# regulators.net
KiCad netlist of a schematic drawn in Altium Designer
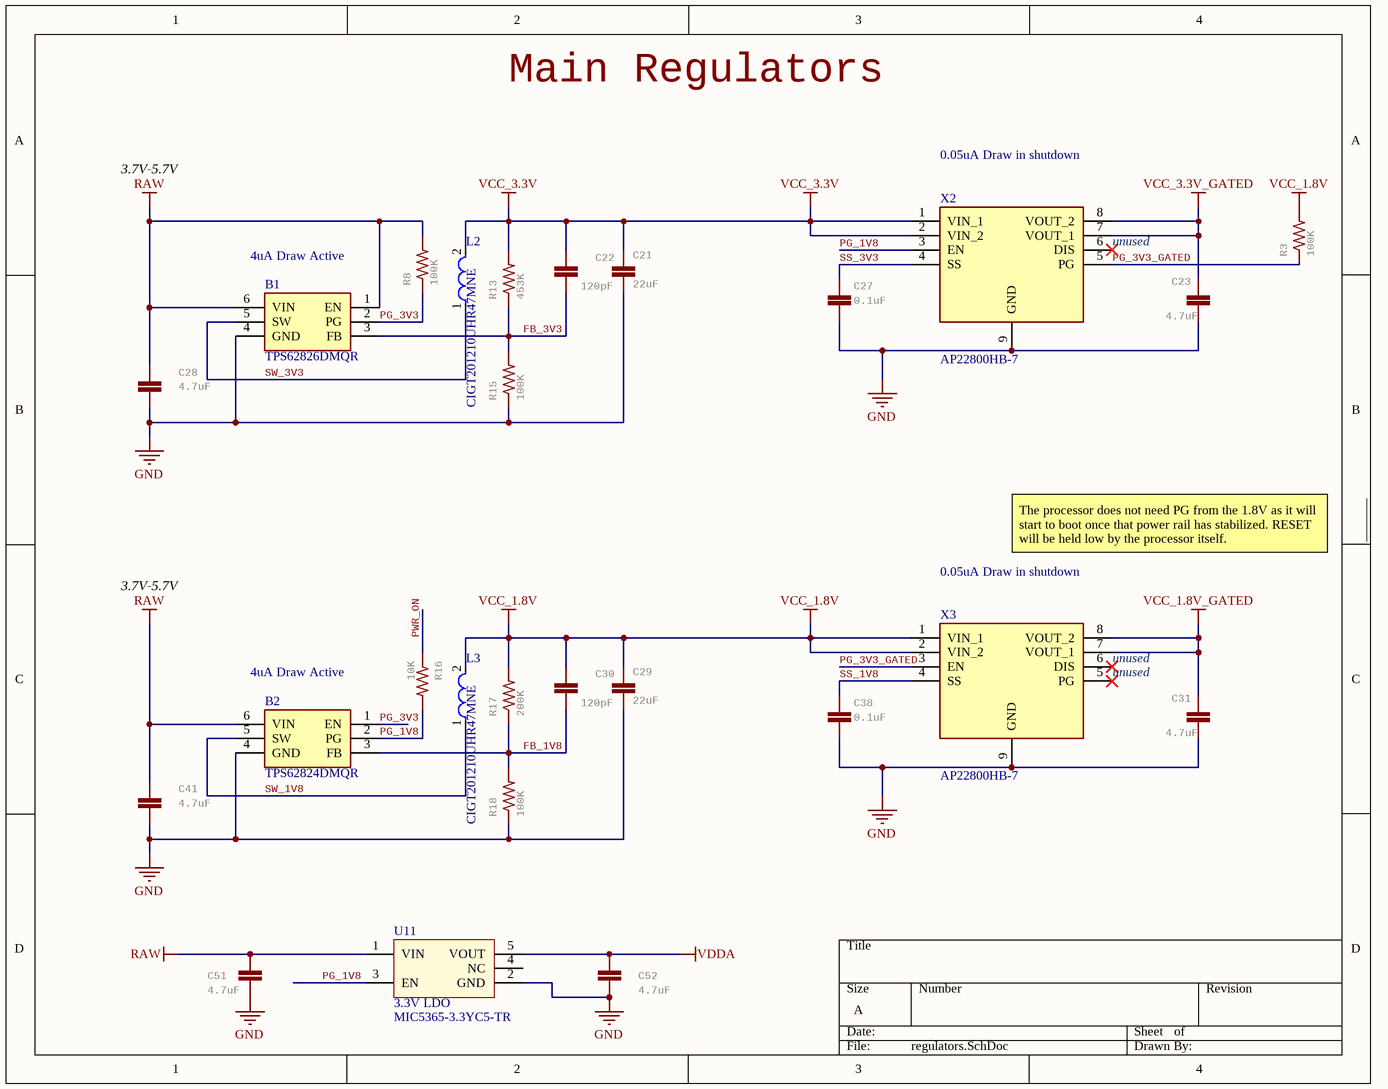
[diagram p0: regulators.SchDoc]

(export (version "E")
  (design (tool "Eeschema 10.0.6"))
  (components
    (comp (ref "B1")
      (value "TPS62826DMQR")
      (footprint "TPS62826ADMQR")
      (fields (field (name "MOUSER PART NUMBER") "595-TPS62826DMQR"))
      (libsource (lib "openmv-ae3") (part "TPS62826ADMQR"))
    )
    (comp (ref "B2")
      (value "TPS62824DMQR")
      (footprint "TPS62826ADMQR")
      (fields (field (name "MOUSER PART NUMBER") "595-TPS62824DMQR"))
      (libsource (lib "openmv-ae3") (part "TPS62826ADMQR"))
    )
    (comp (ref "C21")
      (value "22uF")
      (footprint "0805")
      (fields (field (name "MPN") "CL21A226MQQNNNE"))
      (libsource (lib "openmv-ae3") (part "22UF-0805-6.3V-20%"))
    )
    (comp (ref "C22")
      (value "120pF")
      (footprint "0402-CAP")
      (description "CapacitorStandard 0603 ceramic capacitor, and 0.1\" leaded capacitor.")
      (fields (field (name "MPN") "GRM1555C2A121GE01D"))
      (libsource (lib "openmv-ae3") (part "CAP0402-CAP"))
    )
    (comp (ref "C23")
      (value "4.7uF")
      (footprint "0402-CAP")
      (description "CapacitorStandard 0603 ceramic capacitor, and 0.1\" leaded capacitor.")
      (fields (field (name "MPN") "JMK105BBJ475MV-F"))
      (libsource (lib "") (part "CAP0402-CAP_1"))
    )
    (comp (ref "C27")
      (value "0.1uF")
      (footprint "0402-CAP")
      (description "CAPACITOR, European symbol")
      (fields (field (name "MPN") "C0402C104Z4VAC"))
      (libsource (lib "rt10") (part "C-EUC0201"))
    )
    (comp (ref "C28")
      (value "4.7uF")
      (footprint "0402-CAP")
      (description "CapacitorStandard 0603 ceramic capacitor, and 0.1\" leaded capacitor.")
      (fields (field (name "MPN") "JMK105BBJ475MV-F"))
      (libsource (lib "openmv-ae3") (part "CAP0402-CAP"))
    )
    (comp (ref "C29")
      (value "22uF")
      (footprint "0805")
      (fields (field (name "MPN") "CL21A226MQQNNNE"))
      (libsource (lib "openmv-ae3") (part "22UF-0805-6.3V-20%"))
    )
    (comp (ref "C30")
      (value "120pF")
      (footprint "0402-CAP")
      (description "CapacitorStandard 0603 ceramic capacitor, and 0.1\" leaded capacitor.")
      (fields (field (name "MPN") "GRM1555C2A121GE01D"))
      (libsource (lib "openmv-ae3") (part "CAP0402-CAP"))
    )
    (comp (ref "C31")
      (value "4.7uF")
      (footprint "0402-CAP")
      (description "CapacitorStandard 0603 ceramic capacitor, and 0.1\" leaded capacitor.")
      (fields (field (name "MPN") "JMK105BBJ475MV-F"))
      (libsource (lib "") (part "CAP0402-CAP_1"))
    )
    (comp (ref "C38")
      (value "0.1uF")
      (footprint "0402-CAP")
      (description "CAPACITOR, European symbol")
      (fields (field (name "MPN") "C0402C104Z4VAC"))
      (libsource (lib "rt10") (part "C-EUC0201"))
    )
    (comp (ref "C41")
      (value "4.7uF")
      (footprint "0402-CAP")
      (description "CapacitorStandard 0603 ceramic capacitor, and 0.1\" leaded capacitor.")
      (fields (field (name "MPN") "JMK105BBJ475MV-F"))
      (libsource (lib "openmv-ae3") (part "CAP0402-CAP"))
    )
    (comp (ref "C51")
      (value "4.7uF")
      (footprint "0402-CAP")
      (description "CapacitorStandard 0603 ceramic capacitor, and 0.1\" leaded capacitor.")
      (fields (field (name "MPN") "JMK105BBJ475MV-F"))
      (libsource (lib "openmv-ae3") (part "CAP0402-CAP"))
    )
    (comp (ref "C52")
      (value "4.7uF")
      (footprint "0402-CAP")
      (description "CapacitorStandard 0603 ceramic capacitor, and 0.1\" leaded capacitor.")
      (fields (field (name "MPN") "JMK105BBJ475MV-F"))
      (libsource (lib "rt10") (part "CAP0402-CAP"))
    )
    (comp (ref "L2")
      (value "CIGT201210UHR47MNE")
      (footprint "0805")
      (description "Power Inductor : LxW size(mm) 2012 Thickness1 Inductance (uH) 20%: 0.47")
      (fields (field (name "TOLERANCE") "20%"))
      (libsource (lib "openmv-ae3") (part "CMP-00002-1"))
    )
    (comp (ref "L3")
      (value "CIGT201210UHR47MNE")
      (footprint "0805")
      (description "Power Inductor : LxW size(mm) 2012 Thickness1 Inductance (uH) 20%: 0.47")
      (fields (field (name "TOLERANCE") "20%"))
      (libsource (lib "openmv-ae3") (part "CMP-00002-1"))
    )
    (comp (ref "R3")
      (value "100K")
      (footprint "0402-RES")
      (description "ResistorBasic schematic elements and footprints for 0603, 1206, and PTH resistors.")
      (fields (field (name "MPN") "AC0402FR-07100KL"))
      (libsource (lib "rt10") (part "RESISTOR0402-RES"))
    )
    (comp (ref "R8")
      (value "100K")
      (footprint "0402-RES")
      (description "ResistorBasic schematic elements and footprints for 0603, 1206, and PTH resistors.")
      (fields (field (name "MPN") "AC0402FR-07100KL"))
      (libsource (lib "rt10") (part "RESISTOR0402-RES"))
    )
    (comp (ref "R13")
      (value "453K")
      (footprint "0402-RES")
      (description "ResistorBasic schematic elements and footprints for 0603, 1206, and PTH resistors.")
      (fields (field (name "MPN") "CR0402-FX-4533GLF"))
      (libsource (lib "rt10") (part "RESISTOR0402-RES"))
    )
    (comp (ref "R15")
      (value "100K")
      (footprint "0402-RES")
      (description "ResistorBasic schematic elements and footprints for 0603, 1206, and PTH resistors.")
      (fields (field (name "MPN") "AC0402FR-07100KL"))
      (libsource (lib "rt10") (part "RESISTOR0402-RES"))
    )
    (comp (ref "R16")
      (value "10K")
      (footprint "0402-RES")
      (description "ResistorBasic schematic elements and footprints for 0603, 1206, and PTH resistors.")
      (fields (field (name "MPN") "AC0402FR-1310KL"))
      (libsource (lib "rt10") (part "RESISTOR0402-RES"))
    )
    (comp (ref "R17")
      (value "200K")
      (footprint "0402-RES")
      (description "ResistorBasic schematic elements and footprints for 0603, 1206, and PTH resistors.")
      (fields (field (name "MPN") "CR0402-FX-2003GLF"))
      (libsource (lib "rt10") (part "RESISTOR0402-RES"))
    )
    (comp (ref "R18")
      (value "100K")
      (footprint "0402-RES")
      (description "ResistorBasic schematic elements and footprints for 0603, 1206, and PTH resistors.")
      (fields (field (name "MPN") "AC0402FR-07100KL"))
      (libsource (lib "rt10") (part "RESISTOR0402-RES"))
    )
    (comp (ref "U11")
      (value "3.3V LDO")
      (footprint "SC70-5")
      (fields (field (name "MF") "Microchip") (field (name "MPN") "MIC5365-3.3YC5-TR"))
      (libsource (lib "openmv-n6") (part "MIC5365-3.3YC5-TR"))
    )
    (comp (ref "X2")
      (value "AP22800HB-7")
      (footprint "SON50P161X211X60-9N")
      (description "Power Switch ICs - Power Distribution Load Switch")
      (fields (field (name "MOUSER PART NUMBER") "621-AP22800HB-7"))
      (libsource (lib "AP22800HB-7") (part "AP22800HB-7"))
    )
    (comp (ref "X3")
      (value "AP22800HB-7")
      (footprint "SON50P161X211X60-9N")
      (description "Power Switch ICs - Power Distribution Load Switch")
      (fields (field (name "MOUSER PART NUMBER") "621-AP22800HB-7"))
      (libsource (lib "AP22800HB-7") (part "AP22800HB-7"))
    )
  )
  (nets
    (net (code "1") (name "/FB_1V8") (class "Default")
      (node (ref "B2") (pin "3") (pinfunction "FB_3") (pintype "passive"))
      (node (ref "C30") (pin "1") (pinfunction "1_1") (pintype "passive"))
      (node (ref "R17") (pin "1") (pinfunction "1_1") (pintype "passive"))
      (node (ref "R18") (pin "2") (pinfunction "2_2") (pintype "passive"))
    )
    (net (code "2") (name "/FB_3V3") (class "Default")
      (node (ref "B1") (pin "3") (pinfunction "FB_3") (pintype "passive"))
      (node (ref "C22") (pin "1") (pinfunction "1_1") (pintype "passive"))
      (node (ref "R13") (pin "1") (pinfunction "1_1") (pintype "passive"))
      (node (ref "R15") (pin "2") (pinfunction "2_2") (pintype "passive"))
    )
    (net (code "3") (name "/PG_1V8") (class "Default")
      (node (ref "B2") (pin "2") (pinfunction "PG_2") (pintype "passive"))
      (node (ref "R16") (pin "2") (pinfunction "2_2") (pintype "passive"))
      (node (ref "U11") (pin "3") (pinfunction "EN_3") (pintype "passive"))
      (node (ref "X2") (pin "3") (pinfunction "EN_3") (pintype "passive"))
    )
    (net (code "4") (name "/PG_3V3") (class "Default")
      (node (ref "B1") (pin "2") (pinfunction "PG_2") (pintype "passive"))
      (node (ref "B2") (pin "1") (pinfunction "EN_1") (pintype "passive"))
      (node (ref "R8") (pin "1") (pinfunction "1_1") (pintype "passive"))
    )
    (net (code "5") (name "/PG_3V3_GATED") (class "Default")
      (node (ref "R3") (pin "1") (pinfunction "1_1") (pintype "passive"))
      (node (ref "X2") (pin "5") (pinfunction "PG_5") (pintype "passive"))
      (node (ref "X3") (pin "3") (pinfunction "EN_3") (pintype "passive"))
    )
    (net (code "6") (name "/PWR_ON") (class "Default")
      (node (ref "R16") (pin "1") (pinfunction "1_1") (pintype "passive"))
    )
    (net (code "7") (name "/SS_1V8") (class "Default")
      (node (ref "C38") (pin "2") (pinfunction "2_2") (pintype "passive"))
      (node (ref "X3") (pin "4") (pinfunction "SS_4") (pintype "passive"))
    )
    (net (code "8") (name "/SS_3V3") (class "Default")
      (node (ref "C27") (pin "2") (pinfunction "2_2") (pintype "passive"))
      (node (ref "X2") (pin "4") (pinfunction "SS_4") (pintype "passive"))
    )
    (net (code "9") (name "/SW_1V8") (class "Default")
      (node (ref "B2") (pin "5") (pinfunction "SW_5") (pintype "passive"))
      (node (ref "L3") (pin "1") (pinfunction "1_1") (pintype "passive"))
    )
    (net (code "10") (name "/SW_3V3") (class "Default")
      (node (ref "B1") (pin "5") (pinfunction "SW_5") (pintype "passive"))
      (node (ref "L2") (pin "1") (pinfunction "1_1") (pintype "passive"))
    )
    (net (code "11") (name "GND") (class "Default")
      (node (ref "B1") (pin "4") (pinfunction "GND_4") (pintype "passive"))
      (node (ref "B2") (pin "4") (pinfunction "GND_4") (pintype "passive"))
      (node (ref "C21") (pin "2") (pinfunction "2_2") (pintype "passive"))
      (node (ref "C23") (pin "2") (pinfunction "2_2") (pintype "passive"))
      (node (ref "C27") (pin "1") (pinfunction "1_1") (pintype "passive"))
      (node (ref "C28") (pin "1") (pinfunction "1_1") (pintype "passive"))
      (node (ref "C29") (pin "2") (pinfunction "2_2") (pintype "passive"))
      (node (ref "C31") (pin "2") (pinfunction "2_2") (pintype "passive"))
      (node (ref "C38") (pin "1") (pinfunction "1_1") (pintype "passive"))
      (node (ref "C41") (pin "1") (pinfunction "1_1") (pintype "passive"))
      (node (ref "C51") (pin "1") (pinfunction "1_1") (pintype "passive"))
      (node (ref "C52") (pin "2") (pinfunction "2_2") (pintype "passive"))
      (node (ref "R15") (pin "1") (pinfunction "1_1") (pintype "passive"))
      (node (ref "R18") (pin "1") (pinfunction "1_1") (pintype "passive"))
      (node (ref "U11") (pin "2") (pinfunction "GND_2") (pintype "passive"))
      (node (ref "X2") (pin "9") (pinfunction "GND_9") (pintype "passive"))
      (node (ref "X3") (pin "9") (pinfunction "GND_9") (pintype "passive"))
    )
    (net (code "12") (name "RAW") (class "Default")
      (node (ref "B1") (pin "1") (pinfunction "EN_1") (pintype "passive"))
      (node (ref "B1") (pin "6") (pinfunction "VIN_6") (pintype "passive"))
      (node (ref "B2") (pin "6") (pinfunction "VIN_6") (pintype "passive"))
      (node (ref "C28") (pin "2") (pinfunction "2_2") (pintype "passive"))
      (node (ref "C41") (pin "2") (pinfunction "2_2") (pintype "passive"))
      (node (ref "C51") (pin "2") (pinfunction "2_2") (pintype "passive"))
      (node (ref "R8") (pin "2") (pinfunction "2_2") (pintype "passive"))
      (node (ref "U11") (pin "1") (pinfunction "VIN_1") (pintype "passive"))
    )
    (net (code "13") (name "VCC_1.8V") (class "Default")
      (node (ref "C29") (pin "1") (pinfunction "1_1") (pintype "passive"))
      (node (ref "C30") (pin "2") (pinfunction "2_2") (pintype "passive"))
      (node (ref "L3") (pin "2") (pinfunction "2_2") (pintype "passive"))
      (node (ref "R17") (pin "2") (pinfunction "2_2") (pintype "passive"))
      (node (ref "R3") (pin "2") (pinfunction "2_2") (pintype "passive"))
      (node (ref "X3") (pin "1") (pinfunction "VIN_1_1") (pintype "passive"))
      (node (ref "X3") (pin "2") (pinfunction "VIN_2_2") (pintype "passive"))
    )
    (net (code "14") (name "VCC_1.8V_GATED") (class "Default")
      (node (ref "C31") (pin "1") (pinfunction "1_1") (pintype "passive"))
      (node (ref "X3") (pin "7") (pinfunction "VOUT_1_7") (pintype "passive"))
      (node (ref "X3") (pin "8") (pinfunction "VOUT_2_8") (pintype "passive"))
    )
    (net (code "15") (name "VCC_3.3V") (class "Default")
      (node (ref "C21") (pin "1") (pinfunction "1_1") (pintype "passive"))
      (node (ref "C22") (pin "2") (pinfunction "2_2") (pintype "passive"))
      (node (ref "L2") (pin "2") (pinfunction "2_2") (pintype "passive"))
      (node (ref "R13") (pin "2") (pinfunction "2_2") (pintype "passive"))
      (node (ref "X2") (pin "1") (pinfunction "VIN_1_1") (pintype "passive"))
      (node (ref "X2") (pin "2") (pinfunction "VIN_2_2") (pintype "passive"))
    )
    (net (code "16") (name "VCC_3.3V_GATED") (class "Default")
      (node (ref "C23") (pin "1") (pinfunction "1_1") (pintype "passive"))
      (node (ref "X2") (pin "7") (pinfunction "VOUT_1_7") (pintype "passive"))
      (node (ref "X2") (pin "8") (pinfunction "VOUT_2_8") (pintype "passive"))
    )
    (net (code "17") (name "VDDA") (class "Default")
      (node (ref "C52") (pin "1") (pinfunction "1_1") (pintype "passive"))
      (node (ref "U11") (pin "5") (pinfunction "VOUT_5") (pintype "passive"))
    )
    (net (code "18") (name "unconnected-(U11-NC-Pad4)") (class "Default")
      (node (ref "U11") (pin "4") (pinfunction "NC_4") (pintype "passive"))
    )
    (net (code "19") (name "unconnected-(X2-DIS-Pad6)") (class "Default")
      (node (ref "X2") (pin "6") (pinfunction "DIS_6") (pintype "passive+no_connect"))
    )
    (net (code "20") (name "unconnected-(X3-DIS-Pad6)") (class "Default")
      (node (ref "X3") (pin "6") (pinfunction "DIS_6") (pintype "passive+no_connect"))
    )
    (net (code "21") (name "unconnected-(X3-PG-Pad5)") (class "Default")
      (node (ref "X3") (pin "5") (pinfunction "PG_5") (pintype "passive+no_connect"))
    )
  )
)
